# PowerBoard.net
KiCad netlist of a schematic drawn in Altium Designer
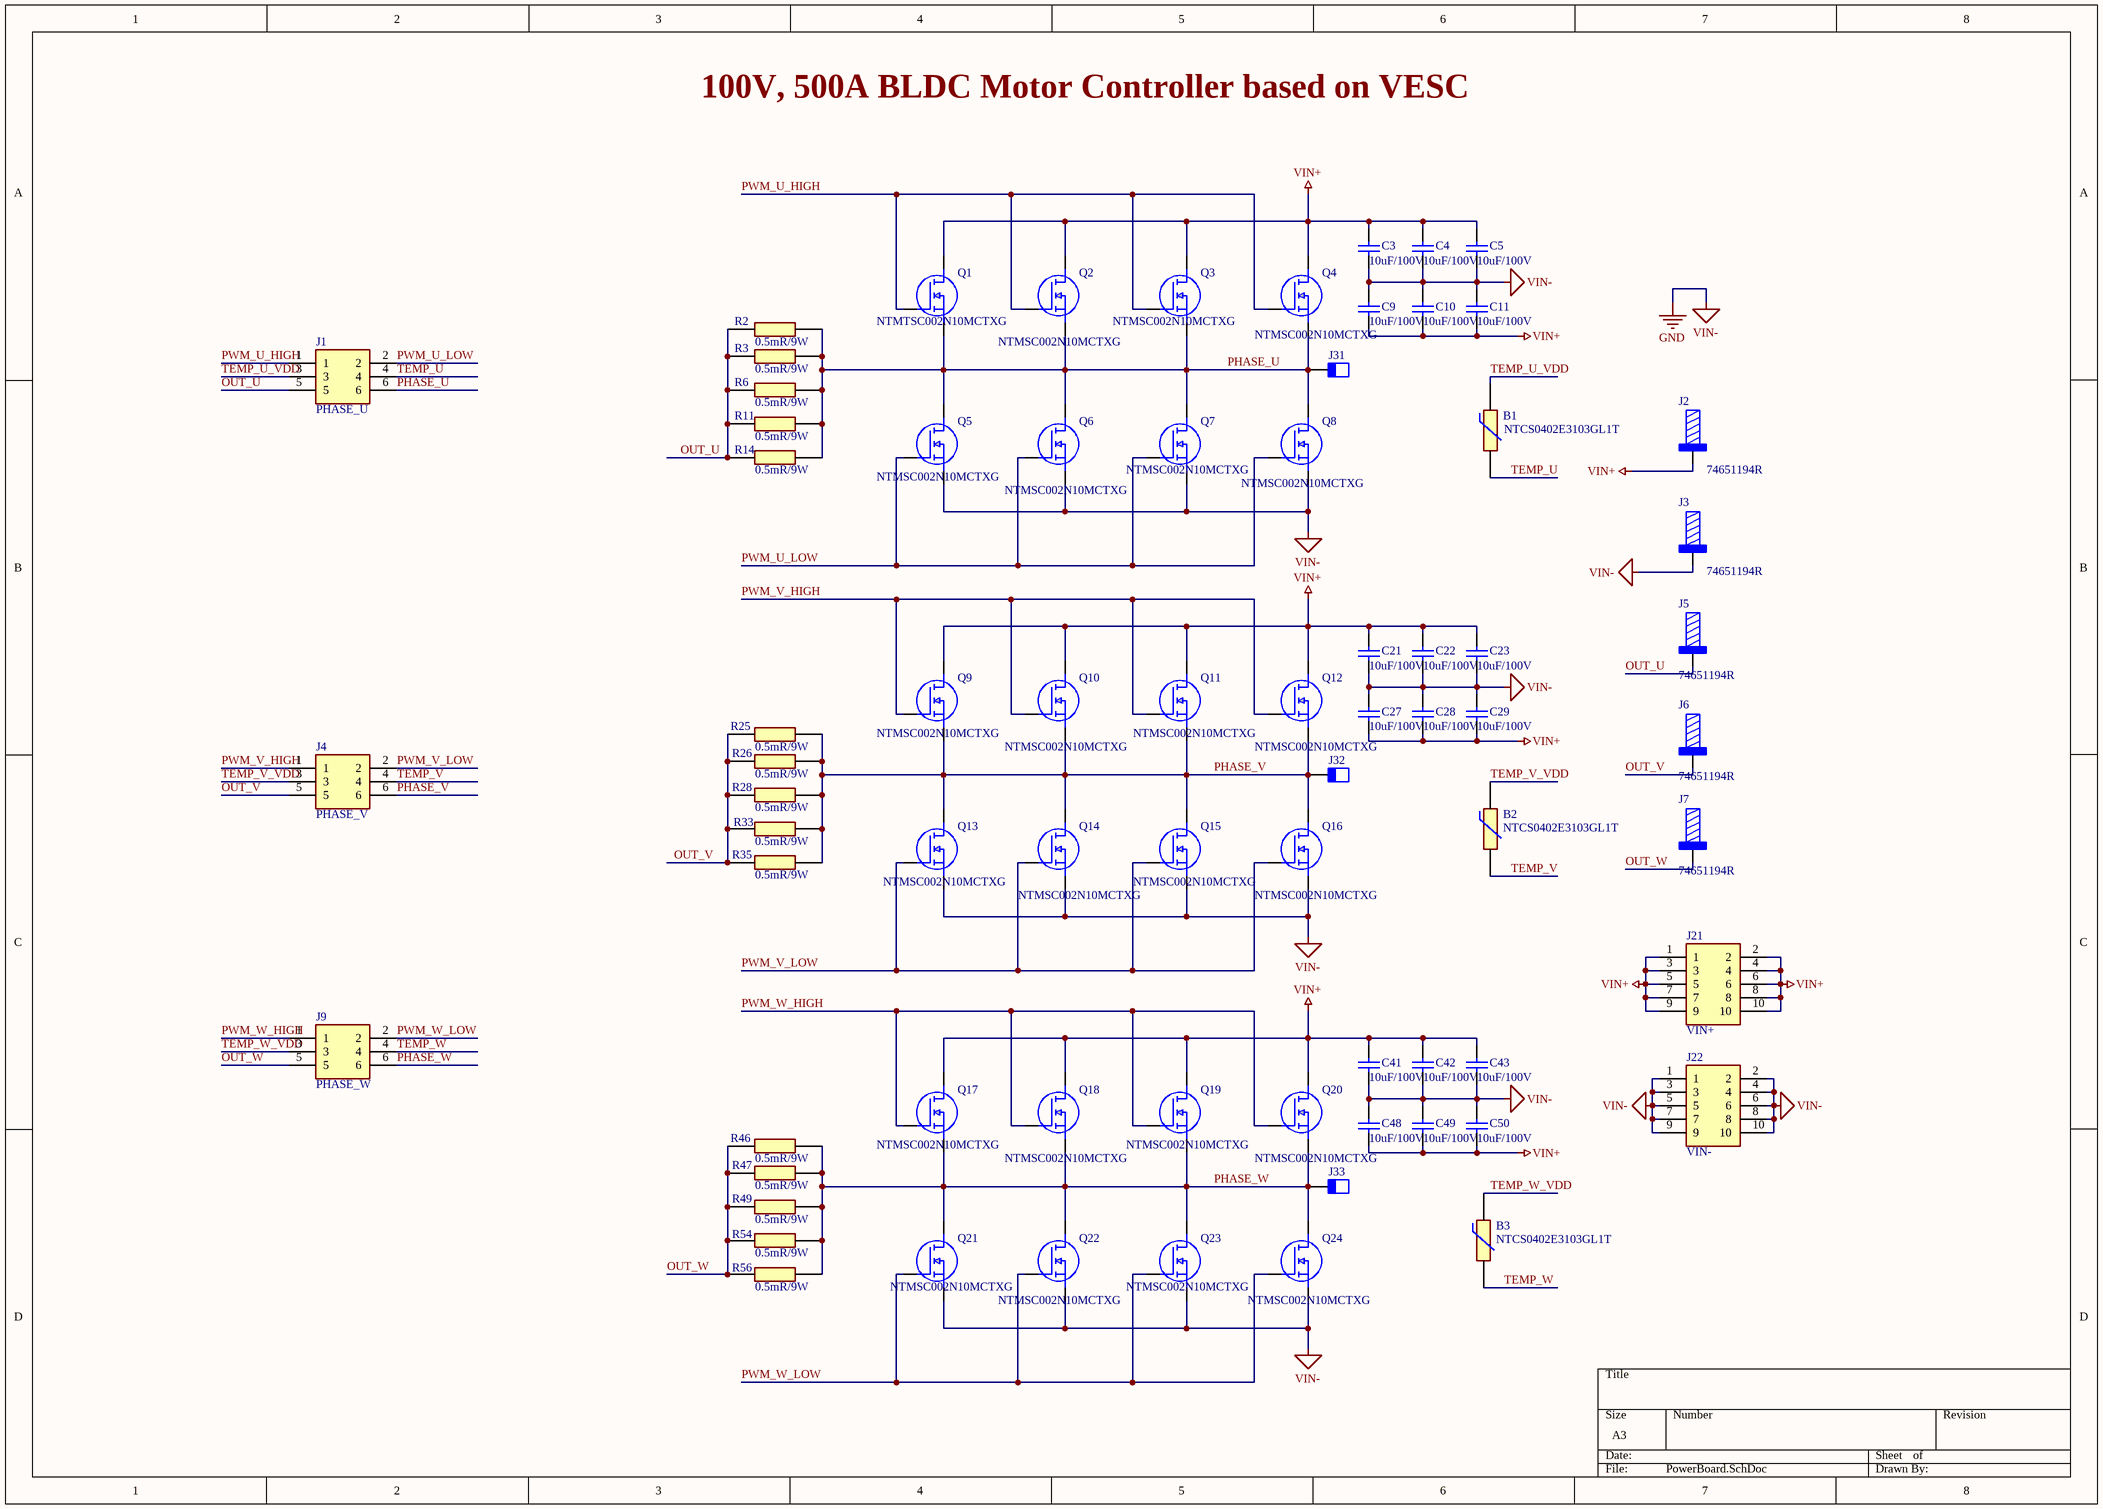
[diagram p0: PowerBoard.SchDoc]

(export (version "E")
  (design (tool "Eeschema 10.0.6"))
  (components
    (comp (ref "B1")
      (value "NTCS0402E3103GL1T")
      (footprint "THRMC1005X65N")
      (description "NTC Thermistors 10Kohms 2% AEC-Q200")
      (fields (field (name "MANUFACTURER") "Vishay"))
      (libsource (lib "VESC_MotorController") (part "NTCS0402E3103GL1T"))
    )
    (comp (ref "B2")
      (value "NTCS0402E3103GL1T")
      (footprint "THRMC1005X65N")
      (description "NTC Thermistors 10Kohms 2% AEC-Q200")
      (fields (field (name "MANUFACTURER") "Vishay"))
      (libsource (lib "VESC_MotorController") (part "NTCS0402E3103GL1T"))
    )
    (comp (ref "B3")
      (value "NTCS0402E3103GL1T")
      (footprint "THRMC1005X65N")
      (description "NTC Thermistors 10Kohms 2% AEC-Q200")
      (fields (field (name "MANUFACTURER") "Vishay"))
      (libsource (lib "VESC_MotorController") (part "NTCS0402E3103GL1T"))
    )
    (comp (ref "C3")
      (value "10uF/100V")
      (footprint "CAPC3225X230N")
      (description "Multilayer Ceramic Capacitors MLCC - SMD/SMT 1210 100VDC 10uF 10% X7R")
      (fields
        (field (name "MANUFACTURER") "TDK")
        (field (name "MANUFACTURER PART NUMBER") "C3225X7R2A106K250AC")
      )
      (libsource (lib "VESC_MotorController") (part "10uF ± 10% 100V"))
    )
    (comp (ref "C4")
      (value "10uF/100V")
      (footprint "CAPC3225X230N")
      (description "Multilayer Ceramic Capacitors MLCC - SMD/SMT 1210 100VDC 10uF 10% X7R")
      (fields
        (field (name "MANUFACTURER") "TDK")
        (field (name "MANUFACTURER PART NUMBER") "C3225X7R2A106K250AC")
      )
      (libsource (lib "VESC_MotorController") (part "10uF ± 10% 100V"))
    )
    (comp (ref "C5")
      (value "10uF/100V")
      (footprint "CAPC3225X230N")
      (description "Multilayer Ceramic Capacitors MLCC - SMD/SMT 1210 100VDC 10uF 10% X7R")
      (fields
        (field (name "MANUFACTURER") "TDK")
        (field (name "MANUFACTURER PART NUMBER") "C3225X7R2A106K250AC")
      )
      (libsource (lib "VESC_MotorController") (part "10uF ± 10% 100V"))
    )
    (comp (ref "C9")
      (value "10uF/100V")
      (footprint "CAPC3225X230N")
      (description "Multilayer Ceramic Capacitors MLCC - SMD/SMT 1210 100VDC 10uF 10% X7R")
      (fields
        (field (name "MANUFACTURER") "TDK")
        (field (name "MANUFACTURER PART NUMBER") "C3225X7R2A106K250AC")
      )
      (libsource (lib "VESC_MotorController") (part "10uF ± 10% 100V"))
    )
    (comp (ref "C10")
      (value "10uF/100V")
      (footprint "CAPC3225X230N")
      (description "Multilayer Ceramic Capacitors MLCC - SMD/SMT 1210 100VDC 10uF 10% X7R")
      (fields
        (field (name "MANUFACTURER") "TDK")
        (field (name "MANUFACTURER PART NUMBER") "C3225X7R2A106K250AC")
      )
      (libsource (lib "VESC_MotorController") (part "10uF ± 10% 100V"))
    )
    (comp (ref "C11")
      (value "10uF/100V")
      (footprint "CAPC3225X230N")
      (description "Multilayer Ceramic Capacitors MLCC - SMD/SMT 1210 100VDC 10uF 10% X7R")
      (fields
        (field (name "MANUFACTURER") "TDK")
        (field (name "MANUFACTURER PART NUMBER") "C3225X7R2A106K250AC")
      )
      (libsource (lib "VESC_MotorController") (part "10uF ± 10% 100V"))
    )
    (comp (ref "C21")
      (value "10uF/100V")
      (footprint "CAPC3225X230N")
      (description "Multilayer Ceramic Capacitors MLCC - SMD/SMT 1210 100VDC 10uF 10% X7R")
      (fields
        (field (name "MANUFACTURER") "TDK")
        (field (name "MANUFACTURER PART NUMBER") "C3225X7R2A106K250AC")
      )
      (libsource (lib "VESC_MotorController") (part "10uF ± 10% 100V"))
    )
    (comp (ref "C22")
      (value "10uF/100V")
      (footprint "CAPC3225X230N")
      (description "Multilayer Ceramic Capacitors MLCC - SMD/SMT 1210 100VDC 10uF 10% X7R")
      (fields
        (field (name "MANUFACTURER") "TDK")
        (field (name "MANUFACTURER PART NUMBER") "C3225X7R2A106K250AC")
      )
      (libsource (lib "VESC_MotorController") (part "10uF ± 10% 100V"))
    )
    (comp (ref "C23")
      (value "10uF/100V")
      (footprint "CAPC3225X230N")
      (description "Multilayer Ceramic Capacitors MLCC - SMD/SMT 1210 100VDC 10uF 10% X7R")
      (fields
        (field (name "MANUFACTURER") "TDK")
        (field (name "MANUFACTURER PART NUMBER") "C3225X7R2A106K250AC")
      )
      (libsource (lib "VESC_MotorController") (part "10uF ± 10% 100V"))
    )
    (comp (ref "C27")
      (value "10uF/100V")
      (footprint "CAPC3225X230N")
      (description "Multilayer Ceramic Capacitors MLCC - SMD/SMT 1210 100VDC 10uF 10% X7R")
      (fields
        (field (name "MANUFACTURER") "TDK")
        (field (name "MANUFACTURER PART NUMBER") "C3225X7R2A106K250AC")
      )
      (libsource (lib "VESC_MotorController") (part "10uF ± 10% 100V"))
    )
    (comp (ref "C28")
      (value "10uF/100V")
      (footprint "CAPC3225X230N")
      (description "Multilayer Ceramic Capacitors MLCC - SMD/SMT 1210 100VDC 10uF 10% X7R")
      (fields
        (field (name "MANUFACTURER") "TDK")
        (field (name "MANUFACTURER PART NUMBER") "C3225X7R2A106K250AC")
      )
      (libsource (lib "VESC_MotorController") (part "10uF ± 10% 100V"))
    )
    (comp (ref "C29")
      (value "10uF/100V")
      (footprint "CAPC3225X230N")
      (description "Multilayer Ceramic Capacitors MLCC - SMD/SMT 1210 100VDC 10uF 10% X7R")
      (fields
        (field (name "MANUFACTURER") "TDK")
        (field (name "MANUFACTURER PART NUMBER") "C3225X7R2A106K250AC")
      )
      (libsource (lib "VESC_MotorController") (part "10uF ± 10% 100V"))
    )
    (comp (ref "C41")
      (value "10uF/100V")
      (footprint "CAPC3225X230N")
      (description "Multilayer Ceramic Capacitors MLCC - SMD/SMT 1210 100VDC 10uF 10% X7R")
      (fields
        (field (name "MANUFACTURER") "TDK")
        (field (name "MANUFACTURER PART NUMBER") "C3225X7R2A106K250AC")
      )
      (libsource (lib "VESC_MotorController") (part "10uF ± 10% 100V"))
    )
    (comp (ref "C42")
      (value "10uF/100V")
      (footprint "CAPC3225X230N")
      (description "Multilayer Ceramic Capacitors MLCC - SMD/SMT 1210 100VDC 10uF 10% X7R")
      (fields
        (field (name "MANUFACTURER") "TDK")
        (field (name "MANUFACTURER PART NUMBER") "C3225X7R2A106K250AC")
      )
      (libsource (lib "VESC_MotorController") (part "10uF ± 10% 100V"))
    )
    (comp (ref "C43")
      (value "10uF/100V")
      (footprint "CAPC3225X230N")
      (description "Multilayer Ceramic Capacitors MLCC - SMD/SMT 1210 100VDC 10uF 10% X7R")
      (fields
        (field (name "MANUFACTURER") "TDK")
        (field (name "MANUFACTURER PART NUMBER") "C3225X7R2A106K250AC")
      )
      (libsource (lib "VESC_MotorController") (part "10uF ± 10% 100V"))
    )
    (comp (ref "C48")
      (value "10uF/100V")
      (footprint "CAPC3225X230N")
      (description "Multilayer Ceramic Capacitors MLCC - SMD/SMT 1210 100VDC 10uF 10% X7R")
      (fields
        (field (name "MANUFACTURER") "TDK")
        (field (name "MANUFACTURER PART NUMBER") "C3225X7R2A106K250AC")
      )
      (libsource (lib "VESC_MotorController") (part "10uF ± 10% 100V"))
    )
    (comp (ref "C49")
      (value "10uF/100V")
      (footprint "CAPC3225X230N")
      (description "Multilayer Ceramic Capacitors MLCC - SMD/SMT 1210 100VDC 10uF 10% X7R")
      (fields
        (field (name "MANUFACTURER") "TDK")
        (field (name "MANUFACTURER PART NUMBER") "C3225X7R2A106K250AC")
      )
      (libsource (lib "VESC_MotorController") (part "10uF ± 10% 100V"))
    )
    (comp (ref "C50")
      (value "10uF/100V")
      (footprint "CAPC3225X230N")
      (description "Multilayer Ceramic Capacitors MLCC - SMD/SMT 1210 100VDC 10uF 10% X7R")
      (fields
        (field (name "MANUFACTURER") "TDK")
        (field (name "MANUFACTURER PART NUMBER") "C3225X7R2A106K250AC")
      )
      (libsource (lib "VESC_MotorController") (part "10uF ± 10% 100V"))
    )
    (comp (ref "J1")
      (value "PHASE_U")
      (footprint "61030621821")
      (description "Headers & Wire Housings WERI Header 2,54 mm SMT")
      (fields
        (field (name "MANUFACTURER") "Wurth Elektronik")
        (field (name "MANUFACTURER PART NUMBER") "61030621821")
      )
      (libsource (lib "VESC_MotorController") (part "Female Header 6 Pin_1"))
    )
    (comp (ref "J2")
      (value "74651194R")
      (footprint "COPPER_CON1")
      (description "WP-THRSH REDCUBE THR with external thread, M4 x 5mm, 85A")
      (fields (field (name "MANUFACTURER") "Wurth Elektronik"))
      (libsource (lib "VESC_MotorController") (part "CopperCon1"))
    )
    (comp (ref "J3")
      (value "74651194R")
      (footprint "COPPER_CON1")
      (description "WP-THRSH REDCUBE THR with external thread, M4 x 5mm, 85A")
      (fields (field (name "MANUFACTURER") "Wurth Elektronik"))
      (libsource (lib "VESC_MotorController") (part "CopperCon1"))
    )
    (comp (ref "J4")
      (value "PHASE_V")
      (footprint "61030621821")
      (description "Headers & Wire Housings WERI Header 2,54 mm SMT")
      (fields
        (field (name "MANUFACTURER") "Wurth Elektronik")
        (field (name "MANUFACTURER PART NUMBER") "61030621821")
      )
      (libsource (lib "VESC_MotorController") (part "Female Header 6 Pin_1"))
    )
    (comp (ref "J5")
      (value "74651194R")
      (footprint "COPPER_CON3")
      (description "WP-THRSH REDCUBE THR with external thread, M4 x 5mm, 85A")
      (fields (field (name "MANUFACTURER") "Wurth Elektronik"))
      (libsource (lib "VESC_MotorController") (part "CopperCon3"))
    )
    (comp (ref "J6")
      (value "74651194R")
      (footprint "COPPER_CON3")
      (description "WP-THRSH REDCUBE THR with external thread, M4 x 5mm, 85A")
      (fields (field (name "MANUFACTURER") "Wurth Elektronik"))
      (libsource (lib "VESC_MotorController") (part "CopperCon3"))
    )
    (comp (ref "J7")
      (value "74651194R")
      (footprint "COPPER_CON3")
      (description "WP-THRSH REDCUBE THR with external thread, M4 x 5mm, 85A")
      (fields (field (name "MANUFACTURER") "Wurth Elektronik"))
      (libsource (lib "VESC_MotorController") (part "CopperCon3"))
    )
    (comp (ref "J9")
      (value "PHASE_W")
      (footprint "61030621821")
      (description "Headers & Wire Housings WERI Header 2,54 mm SMT")
      (fields
        (field (name "MANUFACTURER") "Wurth Elektronik")
        (field (name "MANUFACTURER PART NUMBER") "61030621821")
      )
      (libsource (lib "VESC_MotorController") (part "Female Header 6 Pin_1"))
    )
    (comp (ref "J21")
      (value "VIN+")
      (footprint "61031021821")
      (description "Headers & Wire Housings WR-PHD 250VAC 3A Gry 2Row 10Pos Strgt")
      (fields
        (field (name "MANUFACTURER") "Wurth Elektronik")
        (field (name "MANUFACTURER PART NUMBER") "61031021821")
      )
      (libsource (lib "VESC_MotorController") (part "Female Header 10 Pin_1"))
    )
    (comp (ref "J22")
      (value "VIN-")
      (footprint "61031021821")
      (description "Headers & Wire Housings WR-PHD 250VAC 3A Gry 2Row 10Pos Strgt")
      (fields
        (field (name "MANUFACTURER") "Wurth Elektronik")
        (field (name "MANUFACTURER PART NUMBER") "61031021821")
      )
      (libsource (lib "VESC_MotorController") (part "Female Header 10 Pin_1"))
    )
    (comp (ref "J31")
      (value "~")
      (footprint "COPPER_BUS")
      (description "WP-THRSH REDCUBE THR with external thread, M4 x 5mm, 85A")
      (fields
        (field (name "MANUFACTURER PART NUMBER") "74651194R")
        (field (name "MANUFACTURER") "Wurth Elektronik")
      )
      (libsource (lib "VESC_MotorController") (part "CopperBus"))
    )
    (comp (ref "J32")
      (value "~")
      (footprint "COPPER_BUS")
      (description "WP-THRSH REDCUBE THR with external thread, M4 x 5mm, 85A")
      (fields
        (field (name "MANUFACTURER PART NUMBER") "74651194R")
        (field (name "MANUFACTURER") "Wurth Elektronik")
      )
      (libsource (lib "VESC_MotorController") (part "CopperBus"))
    )
    (comp (ref "J33")
      (value "~")
      (footprint "COPPER_BUS")
      (description "WP-THRSH REDCUBE THR with external thread, M4 x 5mm, 85A")
      (fields
        (field (name "MANUFACTURER PART NUMBER") "74651194R")
        (field (name "MANUFACTURER") "Wurth Elektronik")
      )
      (libsource (lib "VESC_MotorController") (part "CopperBus"))
    )
    (comp (ref "Q1")
      (value "NTMTSC002N10MCTXG")
      (footprint "NTMSC002N10MCTXG")
      (description "MOSFET Single N-Channel Power MOSFET 100V, 236A, 2.0mohm")
      (fields (field (name "MANUFACTURER") "Onsemi"))
      (libsource (lib "VESC_MotorController") (part "NTMSC002N10MCTXG"))
    )
    (comp (ref "Q2")
      (value "NTMSC002N10MCTXG")
      (footprint "NTMSC002N10MCTXG")
      (description "MOSFET Single N-Channel Power MOSFET 100V, 236A, 2.0mohm")
      (fields
        (field (name "MANUFACTURER") "Onsemi")
        (field (name "MANUFACTURER PART NUMBER") "NTMTSC002N10MCTXG")
      )
      (libsource (lib "VESC_MotorController") (part "NTMSC002N10MCTXG"))
    )
    (comp (ref "Q3")
      (value "NTMSC002N10MCTXG")
      (footprint "NTMSC002N10MCTXG")
      (description "MOSFET Single N-Channel Power MOSFET 100V, 236A, 2.0mohm")
      (fields
        (field (name "MANUFACTURER") "Onsemi")
        (field (name "MANUFACTURER PART NUMBER") "NTMTSC002N10MCTXG")
      )
      (libsource (lib "VESC_MotorController") (part "NTMSC002N10MCTXG"))
    )
    (comp (ref "Q4")
      (value "NTMSC002N10MCTXG")
      (footprint "NTMSC002N10MCTXG")
      (description "MOSFET Single N-Channel Power MOSFET 100V, 236A, 2.0mohm")
      (fields
        (field (name "MANUFACTURER") "Onsemi")
        (field (name "MANUFACTURER PART NUMBER") "NTMTSC002N10MCTXG")
      )
      (libsource (lib "VESC_MotorController") (part "NTMSC002N10MCTXG"))
    )
    (comp (ref "Q5")
      (value "NTMSC002N10MCTXG")
      (footprint "NTMSC002N10MCTXG")
      (description "MOSFET Single N-Channel Power MOSFET 100V, 236A, 2.0mohm")
      (fields
        (field (name "MANUFACTURER") "Onsemi")
        (field (name "MANUFACTURER PART NUMBER") "NTMTSC002N10MCTXG")
      )
      (libsource (lib "VESC_MotorController") (part "NTMSC002N10MCTXG"))
    )
    (comp (ref "Q6")
      (value "NTMSC002N10MCTXG")
      (footprint "NTMSC002N10MCTXG")
      (description "MOSFET Single N-Channel Power MOSFET 100V, 236A, 2.0mohm")
      (fields
        (field (name "MANUFACTURER") "Onsemi")
        (field (name "MANUFACTURER PART NUMBER") "NTMTSC002N10MCTXG")
      )
      (libsource (lib "VESC_MotorController") (part "NTMSC002N10MCTXG"))
    )
    (comp (ref "Q7")
      (value "NTMSC002N10MCTXG")
      (footprint "NTMSC002N10MCTXG")
      (description "MOSFET Single N-Channel Power MOSFET 100V, 236A, 2.0mohm")
      (fields
        (field (name "MANUFACTURER") "Onsemi")
        (field (name "MANUFACTURER PART NUMBER") "NTMTSC002N10MCTXG")
      )
      (libsource (lib "VESC_MotorController") (part "NTMSC002N10MCTXG"))
    )
    (comp (ref "Q8")
      (value "NTMSC002N10MCTXG")
      (footprint "NTMSC002N10MCTXG")
      (description "MOSFET Single N-Channel Power MOSFET 100V, 236A, 2.0mohm")
      (fields
        (field (name "MANUFACTURER") "Onsemi")
        (field (name "MANUFACTURER PART NUMBER") "NTMTSC002N10MCTXG")
      )
      (libsource (lib "VESC_MotorController") (part "NTMSC002N10MCTXG"))
    )
    (comp (ref "Q9")
      (value "NTMSC002N10MCTXG")
      (footprint "NTMSC002N10MCTXG")
      (description "MOSFET Single N-Channel Power MOSFET 100V, 236A, 2.0mohm")
      (fields
        (field (name "MANUFACTURER") "Onsemi")
        (field (name "MANUFACTURER PART NUMBER") "NTMTSC002N10MCTXG")
      )
      (libsource (lib "VESC_MotorController") (part "NTMSC002N10MCTXG"))
    )
    (comp (ref "Q10")
      (value "NTMSC002N10MCTXG")
      (footprint "NTMSC002N10MCTXG")
      (description "MOSFET Single N-Channel Power MOSFET 100V, 236A, 2.0mohm")
      (fields
        (field (name "MANUFACTURER") "Onsemi")
        (field (name "MANUFACTURER PART NUMBER") "NTMTSC002N10MCTXG")
      )
      (libsource (lib "VESC_MotorController") (part "NTMSC002N10MCTXG"))
    )
    (comp (ref "Q11")
      (value "NTMSC002N10MCTXG")
      (footprint "NTMSC002N10MCTXG")
      (description "MOSFET Single N-Channel Power MOSFET 100V, 236A, 2.0mohm")
      (fields
        (field (name "MANUFACTURER") "Onsemi")
        (field (name "MANUFACTURER PART NUMBER") "NTMTSC002N10MCTXG")
      )
      (libsource (lib "VESC_MotorController") (part "NTMSC002N10MCTXG"))
    )
    (comp (ref "Q12")
      (value "NTMSC002N10MCTXG")
      (footprint "NTMSC002N10MCTXG")
      (description "MOSFET Single N-Channel Power MOSFET 100V, 236A, 2.0mohm")
      (fields
        (field (name "MANUFACTURER") "Onsemi")
        (field (name "MANUFACTURER PART NUMBER") "NTMTSC002N10MCTXG")
      )
      (libsource (lib "VESC_MotorController") (part "NTMSC002N10MCTXG"))
    )
    (comp (ref "Q13")
      (value "NTMSC002N10MCTXG")
      (footprint "NTMSC002N10MCTXG")
      (description "MOSFET Single N-Channel Power MOSFET 100V, 236A, 2.0mohm")
      (fields
        (field (name "MANUFACTURER") "Onsemi")
        (field (name "MANUFACTURER PART NUMBER") "NTMTSC002N10MCTXG")
      )
      (libsource (lib "VESC_MotorController") (part "NTMSC002N10MCTXG"))
    )
    (comp (ref "Q14")
      (value "NTMSC002N10MCTXG")
      (footprint "NTMSC002N10MCTXG")
      (description "MOSFET Single N-Channel Power MOSFET 100V, 236A, 2.0mohm")
      (fields
        (field (name "MANUFACTURER") "Onsemi")
        (field (name "MANUFACTURER PART NUMBER") "NTMTSC002N10MCTXG")
      )
      (libsource (lib "VESC_MotorController") (part "NTMSC002N10MCTXG"))
    )
    (comp (ref "Q15")
      (value "NTMSC002N10MCTXG")
      (footprint "NTMSC002N10MCTXG")
      (description "MOSFET Single N-Channel Power MOSFET 100V, 236A, 2.0mohm")
      (fields
        (field (name "MANUFACTURER") "Onsemi")
        (field (name "MANUFACTURER PART NUMBER") "NTMTSC002N10MCTXG")
      )
      (libsource (lib "VESC_MotorController") (part "NTMSC002N10MCTXG"))
    )
    (comp (ref "Q16")
      (value "NTMSC002N10MCTXG")
      (footprint "NTMSC002N10MCTXG")
      (description "MOSFET Single N-Channel Power MOSFET 100V, 236A, 2.0mohm")
      (fields
        (field (name "MANUFACTURER") "Onsemi")
        (field (name "MANUFACTURER PART NUMBER") "NTMTSC002N10MCTXG")
      )
      (libsource (lib "VESC_MotorController") (part "NTMSC002N10MCTXG"))
    )
    (comp (ref "Q17")
      (value "NTMSC002N10MCTXG")
      (footprint "NTMSC002N10MCTXG")
      (description "MOSFET Single N-Channel Power MOSFET 100V, 236A, 2.0mohm")
      (fields
        (field (name "MANUFACTURER") "Onsemi")
        (field (name "MANUFACTURER PART NUMBER") "NTMTSC002N10MCTXG")
      )
      (libsource (lib "VESC_MotorController") (part "NTMSC002N10MCTXG"))
    )
    (comp (ref "Q18")
      (value "NTMSC002N10MCTXG")
      (footprint "NTMSC002N10MCTXG")
      (description "MOSFET Single N-Channel Power MOSFET 100V, 236A, 2.0mohm")
      (fields
        (field (name "MANUFACTURER") "Onsemi")
        (field (name "MANUFACTURER PART NUMBER") "NTMTSC002N10MCTXG")
      )
      (libsource (lib "VESC_MotorController") (part "NTMSC002N10MCTXG"))
    )
    (comp (ref "Q19")
      (value "NTMSC002N10MCTXG")
      (footprint "NTMSC002N10MCTXG")
      (description "MOSFET Single N-Channel Power MOSFET 100V, 236A, 2.0mohm")
      (fields
        (field (name "MANUFACTURER") "Onsemi")
        (field (name "MANUFACTURER PART NUMBER") "NTMTSC002N10MCTXG")
      )
      (libsource (lib "VESC_MotorController") (part "NTMSC002N10MCTXG"))
    )
    (comp (ref "Q20")
      (value "NTMSC002N10MCTXG")
      (footprint "NTMSC002N10MCTXG")
      (description "MOSFET Single N-Channel Power MOSFET 100V, 236A, 2.0mohm")
      (fields
        (field (name "MANUFACTURER") "Onsemi")
        (field (name "MANUFACTURER PART NUMBER") "NTMTSC002N10MCTXG")
      )
      (libsource (lib "VESC_MotorController") (part "NTMSC002N10MCTXG"))
    )
    (comp (ref "Q21")
      (value "NTMSC002N10MCTXG")
      (footprint "NTMSC002N10MCTXG")
      (description "MOSFET Single N-Channel Power MOSFET 100V, 236A, 2.0mohm")
      (fields
        (field (name "MANUFACTURER") "Onsemi")
        (field (name "MANUFACTURER PART NUMBER") "NTMTSC002N10MCTXG")
      )
      (libsource (lib "VESC_MotorController") (part "NTMSC002N10MCTXG"))
    )
    (comp (ref "Q22")
      (value "NTMSC002N10MCTXG")
      (footprint "NTMSC002N10MCTXG")
      (description "MOSFET Single N-Channel Power MOSFET 100V, 236A, 2.0mohm")
      (fields
        (field (name "MANUFACTURER") "Onsemi")
        (field (name "MANUFACTURER PART NUMBER") "NTMTSC002N10MCTXG")
      )
      (libsource (lib "VESC_MotorController") (part "NTMSC002N10MCTXG"))
    )
    (comp (ref "Q23")
      (value "NTMSC002N10MCTXG")
      (footprint "NTMSC002N10MCTXG")
      (description "MOSFET Single N-Channel Power MOSFET 100V, 236A, 2.0mohm")
      (fields
        (field (name "MANUFACTURER") "Onsemi")
        (field (name "MANUFACTURER PART NUMBER") "NTMTSC002N10MCTXG")
      )
      (libsource (lib "VESC_MotorController") (part "NTMSC002N10MCTXG"))
    )
    (comp (ref "Q24")
      (value "NTMSC002N10MCTXG")
      (footprint "NTMSC002N10MCTXG")
      (description "MOSFET Single N-Channel Power MOSFET 100V, 236A, 2.0mohm")
      (fields
        (field (name "MANUFACTURER") "Onsemi")
        (field (name "MANUFACTURER PART NUMBER") "NTMTSC002N10MCTXG")
      )
      (libsource (lib "VESC_MotorController") (part "NTMSC002N10MCTXG"))
    )
    (comp (ref "R2")
      (value "0.5mR/9W")
      (footprint "RESC10052X137N")
      (description "Current Sense Resistors - SMD 0.5mOHMS 9W 1% AEC-Q200")
      (fields
        (field (name "MANUFACTURER") "Bourns")
        (field (name "MANUFACTURER PART NUMBER") "CSS2H-3920R-L500FE")
      )
      (libsource (lib "VESC_MotorController") (part "CSS2H-3920R-L500FE"))
    )
    (comp (ref "R3")
      (value "0.5mR/9W")
      (footprint "RESC10052X137N")
      (description "Current Sense Resistors - SMD 0.5mOHMS 9W 1% AEC-Q200")
      (fields
        (field (name "MANUFACTURER") "Bourns")
        (field (name "MANUFACTURER PART NUMBER") "CSS2H-3920R-L500FE")
      )
      (libsource (lib "VESC_MotorController") (part "CSS2H-3920R-L500FE"))
    )
    (comp (ref "R6")
      (value "0.5mR/9W")
      (footprint "RESC10052X137N")
      (description "Current Sense Resistors - SMD 0.5mOHMS 9W 1% AEC-Q200")
      (fields
        (field (name "MANUFACTURER") "Bourns")
        (field (name "MANUFACTURER PART NUMBER") "CSS2H-3920R-L500FE")
      )
      (libsource (lib "VESC_MotorController") (part "CSS2H-3920R-L500FE"))
    )
    (comp (ref "R11")
      (value "0.5mR/9W")
      (footprint "RESC10052X137N")
      (description "Current Sense Resistors - SMD 0.5mOHMS 9W 1% AEC-Q200")
      (fields
        (field (name "MANUFACTURER") "Bourns")
        (field (name "MANUFACTURER PART NUMBER") "CSS2H-3920R-L500FE")
      )
      (libsource (lib "VESC_MotorController") (part "CSS2H-3920R-L500FE"))
    )
    (comp (ref "R14")
      (value "0.5mR/9W")
      (footprint "RESC10052X137N")
      (description "Current Sense Resistors - SMD 0.5mOHMS 9W 1% AEC-Q200")
      (fields
        (field (name "MANUFACTURER") "Bourns")
        (field (name "MANUFACTURER PART NUMBER") "CSS2H-3920R-L500FE")
      )
      (libsource (lib "VESC_MotorController") (part "CSS2H-3920R-L500FE"))
    )
    (comp (ref "R25")
      (value "0.5mR/9W")
      (footprint "RESC10052X137N")
      (description "Current Sense Resistors - SMD 0.5mOHMS 9W 1% AEC-Q200")
      (fields
        (field (name "MANUFACTURER") "Bourns")
        (field (name "MANUFACTURER PART NUMBER") "CSS2H-3920R-L500FE")
      )
      (libsource (lib "VESC_MotorController") (part "CSS2H-3920R-L500FE"))
    )
    (comp (ref "R26")
      (value "0.5mR/9W")
      (footprint "RESC10052X137N")
      (description "Current Sense Resistors - SMD 0.5mOHMS 9W 1% AEC-Q200")
      (fields
        (field (name "MANUFACTURER") "Bourns")
        (field (name "MANUFACTURER PART NUMBER") "CSS2H-3920R-L500FE")
      )
      (libsource (lib "VESC_MotorController") (part "CSS2H-3920R-L500FE"))
    )
    (comp (ref "R28")
      (value "0.5mR/9W")
      (footprint "RESC10052X137N")
      (description "Current Sense Resistors - SMD 0.5mOHMS 9W 1% AEC-Q200")
      (fields
        (field (name "MANUFACTURER") "Bourns")
        (field (name "MANUFACTURER PART NUMBER") "CSS2H-3920R-L500FE")
      )
      (libsource (lib "VESC_MotorController") (part "CSS2H-3920R-L500FE"))
    )
    (comp (ref "R33")
      (value "0.5mR/9W")
      (footprint "RESC10052X137N")
      (description "Current Sense Resistors - SMD 0.5mOHMS 9W 1% AEC-Q200")
      (fields
        (field (name "MANUFACTURER") "Bourns")
        (field (name "MANUFACTURER PART NUMBER") "CSS2H-3920R-L500FE")
      )
      (libsource (lib "VESC_MotorController") (part "CSS2H-3920R-L500FE"))
    )
    (comp (ref "R35")
      (value "0.5mR/9W")
      (footprint "RESC10052X137N")
      (description "Current Sense Resistors - SMD 0.5mOHMS 9W 1% AEC-Q200")
      (fields
        (field (name "MANUFACTURER") "Bourns")
        (field (name "MANUFACTURER PART NUMBER") "CSS2H-3920R-L500FE")
      )
      (libsource (lib "VESC_MotorController") (part "CSS2H-3920R-L500FE"))
    )
    (comp (ref "R46")
      (value "0.5mR/9W")
      (footprint "RESC10052X137N")
      (description "Current Sense Resistors - SMD 0.5mOHMS 9W 1% AEC-Q200")
      (fields
        (field (name "MANUFACTURER") "Bourns")
        (field (name "MANUFACTURER PART NUMBER") "CSS2H-3920R-L500FE")
      )
      (libsource (lib "VESC_MotorController") (part "CSS2H-3920R-L500FE"))
    )
    (comp (ref "R47")
      (value "0.5mR/9W")
      (footprint "RESC10052X137N")
      (description "Current Sense Resistors - SMD 0.5mOHMS 9W 1% AEC-Q200")
      (fields
        (field (name "MANUFACTURER") "Bourns")
        (field (name "MANUFACTURER PART NUMBER") "CSS2H-3920R-L500FE")
      )
      (libsource (lib "VESC_MotorController") (part "CSS2H-3920R-L500FE"))
    )
    (comp (ref "R49")
      (value "0.5mR/9W")
      (footprint "RESC10052X137N")
      (description "Current Sense Resistors - SMD 0.5mOHMS 9W 1% AEC-Q200")
      (fields
        (field (name "MANUFACTURER") "Bourns")
        (field (name "MANUFACTURER PART NUMBER") "CSS2H-3920R-L500FE")
      )
      (libsource (lib "VESC_MotorController") (part "CSS2H-3920R-L500FE"))
    )
    (comp (ref "R54")
      (value "0.5mR/9W")
      (footprint "RESC10052X137N")
      (description "Current Sense Resistors - SMD 0.5mOHMS 9W 1% AEC-Q200")
      (fields
        (field (name "MANUFACTURER") "Bourns")
        (field (name "MANUFACTURER PART NUMBER") "CSS2H-3920R-L500FE")
      )
      (libsource (lib "VESC_MotorController") (part "CSS2H-3920R-L500FE"))
    )
    (comp (ref "R56")
      (value "0.5mR/9W")
      (footprint "RESC10052X137N")
      (description "Current Sense Resistors - SMD 0.5mOHMS 9W 1% AEC-Q200")
      (fields
        (field (name "MANUFACTURER") "Bourns")
        (field (name "MANUFACTURER PART NUMBER") "CSS2H-3920R-L500FE")
      )
      (libsource (lib "VESC_MotorController") (part "CSS2H-3920R-L500FE"))
    )
  )
  (nets
    (net (code "1") (name "/OUT_U") (class "Default")
      (node (ref "J1") (pin "5") (pinfunction "5_5") (pintype "passive"))
      (node (ref "J5") (pin "1") (pinfunction "1_1") (pintype "passive"))
      (node (ref "R11") (pin "1") (pinfunction "1_1") (pintype "passive"))
      (node (ref "R14") (pin "1") (pinfunction "1_1") (pintype "passive"))
      (node (ref "R2") (pin "1") (pinfunction "1_1") (pintype "passive"))
      (node (ref "R3") (pin "1") (pinfunction "1_1") (pintype "passive"))
      (node (ref "R6") (pin "1") (pinfunction "1_1") (pintype "passive"))
    )
    (net (code "2") (name "/OUT_V") (class "Default")
      (node (ref "J4") (pin "5") (pinfunction "5_5") (pintype "passive"))
      (node (ref "J6") (pin "1") (pinfunction "1_1") (pintype "passive"))
      (node (ref "R25") (pin "1") (pinfunction "1_1") (pintype "passive"))
      (node (ref "R26") (pin "1") (pinfunction "1_1") (pintype "passive"))
      (node (ref "R28") (pin "1") (pinfunction "1_1") (pintype "passive"))
      (node (ref "R33") (pin "1") (pinfunction "1_1") (pintype "passive"))
      (node (ref "R35") (pin "1") (pinfunction "1_1") (pintype "passive"))
    )
    (net (code "3") (name "/OUT_W") (class "Default")
      (node (ref "J7") (pin "1") (pinfunction "1_1") (pintype "passive"))
      (node (ref "J9") (pin "5") (pinfunction "5_5") (pintype "passive"))
      (node (ref "R46") (pin "1") (pinfunction "1_1") (pintype "passive"))
      (node (ref "R47") (pin "1") (pinfunction "1_1") (pintype "passive"))
      (node (ref "R49") (pin "1") (pinfunction "1_1") (pintype "passive"))
      (node (ref "R54") (pin "1") (pinfunction "1_1") (pintype "passive"))
      (node (ref "R56") (pin "1") (pinfunction "1_1") (pintype "passive"))
    )
    (net (code "4") (name "/PHASE_U") (class "Default")
      (node (ref "J1") (pin "6") (pinfunction "6_6") (pintype "passive"))
      (node (ref "J31") (pin "1") (pinfunction "1_1") (pintype "passive"))
      (node (ref "Q1") (pin "SOURCE") (pinfunction "SOURCE_SOURCE") (pintype "passive"))
      (node (ref "Q2") (pin "SOURCE") (pinfunction "SOURCE_SOURCE") (pintype "passive"))
      (node (ref "Q3") (pin "SOURCE") (pinfunction "SOURCE_SOURCE") (pintype "passive"))
      (node (ref "Q4") (pin "SOURCE") (pinfunction "SOURCE_SOURCE") (pintype "passive"))
      (node (ref "Q5") (pin "DRAIN") (pinfunction "DRAIN_DRAIN") (pintype "passive"))
      (node (ref "Q6") (pin "DRAIN") (pinfunction "DRAIN_DRAIN") (pintype "passive"))
      (node (ref "Q7") (pin "DRAIN") (pinfunction "DRAIN_DRAIN") (pintype "passive"))
      (node (ref "Q8") (pin "DRAIN") (pinfunction "DRAIN_DRAIN") (pintype "passive"))
      (node (ref "R11") (pin "2") (pinfunction "2_2") (pintype "passive"))
      (node (ref "R14") (pin "2") (pinfunction "2_2") (pintype "passive"))
      (node (ref "R2") (pin "2") (pinfunction "2_2") (pintype "passive"))
      (node (ref "R3") (pin "2") (pinfunction "2_2") (pintype "passive"))
      (node (ref "R6") (pin "2") (pinfunction "2_2") (pintype "passive"))
    )
    (net (code "5") (name "/PHASE_V") (class "Default")
      (node (ref "J32") (pin "1") (pinfunction "1_1") (pintype "passive"))
      (node (ref "J4") (pin "6") (pinfunction "6_6") (pintype "passive"))
      (node (ref "Q10") (pin "SOURCE") (pinfunction "SOURCE_SOURCE") (pintype "passive"))
      (node (ref "Q11") (pin "SOURCE") (pinfunction "SOURCE_SOURCE") (pintype "passive"))
      (node (ref "Q12") (pin "SOURCE") (pinfunction "SOURCE_SOURCE") (pintype "passive"))
      (node (ref "Q13") (pin "DRAIN") (pinfunction "DRAIN_DRAIN") (pintype "passive"))
      (node (ref "Q14") (pin "DRAIN") (pinfunction "DRAIN_DRAIN") (pintype "passive"))
      (node (ref "Q15") (pin "DRAIN") (pinfunction "DRAIN_DRAIN") (pintype "passive"))
      (node (ref "Q16") (pin "DRAIN") (pinfunction "DRAIN_DRAIN") (pintype "passive"))
      (node (ref "Q9") (pin "SOURCE") (pinfunction "SOURCE_SOURCE") (pintype "passive"))
      (node (ref "R25") (pin "2") (pinfunction "2_2") (pintype "passive"))
      (node (ref "R26") (pin "2") (pinfunction "2_2") (pintype "passive"))
      (node (ref "R28") (pin "2") (pinfunction "2_2") (pintype "passive"))
      (node (ref "R33") (pin "2") (pinfunction "2_2") (pintype "passive"))
      (node (ref "R35") (pin "2") (pinfunction "2_2") (pintype "passive"))
    )
    (net (code "6") (name "/PHASE_W") (class "Default")
      (node (ref "J33") (pin "1") (pinfunction "1_1") (pintype "passive"))
      (node (ref "J9") (pin "6") (pinfunction "6_6") (pintype "passive"))
      (node (ref "Q17") (pin "SOURCE") (pinfunction "SOURCE_SOURCE") (pintype "passive"))
      (node (ref "Q18") (pin "SOURCE") (pinfunction "SOURCE_SOURCE") (pintype "passive"))
      (node (ref "Q19") (pin "SOURCE") (pinfunction "SOURCE_SOURCE") (pintype "passive"))
      (node (ref "Q20") (pin "SOURCE") (pinfunction "SOURCE_SOURCE") (pintype "passive"))
      (node (ref "Q21") (pin "DRAIN") (pinfunction "DRAIN_DRAIN") (pintype "passive"))
      (node (ref "Q22") (pin "DRAIN") (pinfunction "DRAIN_DRAIN") (pintype "passive"))
      (node (ref "Q23") (pin "DRAIN") (pinfunction "DRAIN_DRAIN") (pintype "passive"))
      (node (ref "Q24") (pin "DRAIN") (pinfunction "DRAIN_DRAIN") (pintype "passive"))
      (node (ref "R46") (pin "2") (pinfunction "2_2") (pintype "passive"))
      (node (ref "R47") (pin "2") (pinfunction "2_2") (pintype "passive"))
      (node (ref "R49") (pin "2") (pinfunction "2_2") (pintype "passive"))
      (node (ref "R54") (pin "2") (pinfunction "2_2") (pintype "passive"))
      (node (ref "R56") (pin "2") (pinfunction "2_2") (pintype "passive"))
    )
    (net (code "7") (name "/PWM_U_HIGH") (class "Default")
      (node (ref "J1") (pin "1") (pinfunction "1_1") (pintype "passive"))
      (node (ref "Q1") (pin "GATE") (pinfunction "GATE_GATE") (pintype "passive"))
      (node (ref "Q2") (pin "GATE") (pinfunction "GATE_GATE") (pintype "passive"))
      (node (ref "Q3") (pin "GATE") (pinfunction "GATE_GATE") (pintype "passive"))
      (node (ref "Q4") (pin "GATE") (pinfunction "GATE_GATE") (pintype "passive"))
    )
    (net (code "8") (name "/PWM_U_LOW") (class "Default")
      (node (ref "J1") (pin "2") (pinfunction "2_2") (pintype "passive"))
      (node (ref "Q5") (pin "GATE") (pinfunction "GATE_GATE") (pintype "passive"))
      (node (ref "Q6") (pin "GATE") (pinfunction "GATE_GATE") (pintype "passive"))
      (node (ref "Q7") (pin "GATE") (pinfunction "GATE_GATE") (pintype "passive"))
      (node (ref "Q8") (pin "GATE") (pinfunction "GATE_GATE") (pintype "passive"))
    )
    (net (code "9") (name "/PWM_V_HIGH") (class "Default")
      (node (ref "J4") (pin "1") (pinfunction "1_1") (pintype "passive"))
      (node (ref "Q10") (pin "GATE") (pinfunction "GATE_GATE") (pintype "passive"))
      (node (ref "Q11") (pin "GATE") (pinfunction "GATE_GATE") (pintype "passive"))
      (node (ref "Q12") (pin "GATE") (pinfunction "GATE_GATE") (pintype "passive"))
      (node (ref "Q9") (pin "GATE") (pinfunction "GATE_GATE") (pintype "passive"))
    )
    (net (code "10") (name "/PWM_V_LOW") (class "Default")
      (node (ref "J4") (pin "2") (pinfunction "2_2") (pintype "passive"))
      (node (ref "Q13") (pin "GATE") (pinfunction "GATE_GATE") (pintype "passive"))
      (node (ref "Q14") (pin "GATE") (pinfunction "GATE_GATE") (pintype "passive"))
      (node (ref "Q15") (pin "GATE") (pinfunction "GATE_GATE") (pintype "passive"))
      (node (ref "Q16") (pin "GATE") (pinfunction "GATE_GATE") (pintype "passive"))
    )
    (net (code "11") (name "/PWM_W_HIGH") (class "Default")
      (node (ref "J9") (pin "1") (pinfunction "1_1") (pintype "passive"))
      (node (ref "Q17") (pin "GATE") (pinfunction "GATE_GATE") (pintype "passive"))
      (node (ref "Q18") (pin "GATE") (pinfunction "GATE_GATE") (pintype "passive"))
      (node (ref "Q19") (pin "GATE") (pinfunction "GATE_GATE") (pintype "passive"))
      (node (ref "Q20") (pin "GATE") (pinfunction "GATE_GATE") (pintype "passive"))
    )
    (net (code "12") (name "/PWM_W_LOW") (class "Default")
      (node (ref "J9") (pin "2") (pinfunction "2_2") (pintype "passive"))
      (node (ref "Q21") (pin "GATE") (pinfunction "GATE_GATE") (pintype "passive"))
      (node (ref "Q22") (pin "GATE") (pinfunction "GATE_GATE") (pintype "passive"))
      (node (ref "Q23") (pin "GATE") (pinfunction "GATE_GATE") (pintype "passive"))
      (node (ref "Q24") (pin "GATE") (pinfunction "GATE_GATE") (pintype "passive"))
    )
    (net (code "13") (name "/TEMP_U") (class "Default")
      (node (ref "B1") (pin "2") (pinfunction "2_2") (pintype "passive"))
      (node (ref "J1") (pin "4") (pinfunction "4_4") (pintype "passive"))
    )
    (net (code "14") (name "/TEMP_U_VDD") (class "Default")
      (node (ref "B1") (pin "1") (pinfunction "1_1") (pintype "passive"))
      (node (ref "J1") (pin "3") (pinfunction "3_3") (pintype "passive"))
    )
    (net (code "15") (name "/TEMP_V") (class "Default")
      (node (ref "B2") (pin "2") (pinfunction "2_2") (pintype "passive"))
      (node (ref "J4") (pin "4") (pinfunction "4_4") (pintype "passive"))
    )
    (net (code "16") (name "/TEMP_V_VDD") (class "Default")
      (node (ref "B2") (pin "1") (pinfunction "1_1") (pintype "passive"))
      (node (ref "J4") (pin "3") (pinfunction "3_3") (pintype "passive"))
    )
    (net (code "17") (name "/TEMP_W") (class "Default")
      (node (ref "B3") (pin "2") (pinfunction "2_2") (pintype "passive"))
      (node (ref "J9") (pin "4") (pinfunction "4_4") (pintype "passive"))
    )
    (net (code "18") (name "/TEMP_W_VDD") (class "Default")
      (node (ref "B3") (pin "1") (pinfunction "1_1") (pintype "passive"))
      (node (ref "J9") (pin "3") (pinfunction "3_3") (pintype "passive"))
    )
    (net (code "19") (name "GND") (class "Default")
      (node (ref "C10") (pin "2") (pinfunction "2_2") (pintype "passive"))
      (node (ref "C11") (pin "2") (pinfunction "2_2") (pintype "passive"))
      (node (ref "C21") (pin "1") (pinfunction "1_1") (pintype "passive"))
      (node (ref "C22") (pin "1") (pinfunction "1_1") (pintype "passive"))
      (node (ref "C23") (pin "1") (pinfunction "1_1") (pintype "passive"))
      (node (ref "C27") (pin "2") (pinfunction "2_2") (pintype "passive"))
      (node (ref "C28") (pin "2") (pinfunction "2_2") (pintype "passive"))
      (node (ref "C29") (pin "2") (pinfunction "2_2") (pintype "passive"))
      (node (ref "C3") (pin "1") (pinfunction "1_1") (pintype "passive"))
      (node (ref "C4") (pin "1") (pinfunction "1_1") (pintype "passive"))
      (node (ref "C41") (pin "1") (pinfunction "1_1") (pintype "passive"))
      (node (ref "C42") (pin "1") (pinfunction "1_1") (pintype "passive"))
      (node (ref "C43") (pin "1") (pinfunction "1_1") (pintype "passive"))
      (node (ref "C48") (pin "2") (pinfunction "2_2") (pintype "passive"))
      (node (ref "C49") (pin "2") (pinfunction "2_2") (pintype "passive"))
      (node (ref "C5") (pin "1") (pinfunction "1_1") (pintype "passive"))
      (node (ref "C50") (pin "2") (pinfunction "2_2") (pintype "passive"))
      (node (ref "C9") (pin "2") (pinfunction "2_2") (pintype "passive"))
      (node (ref "J22") (pin "1") (pinfunction "1_1") (pintype "passive"))
      (node (ref "J22") (pin "10") (pinfunction "10_10") (pintype "passive"))
      (node (ref "J22") (pin "2") (pinfunction "2_2") (pintype "passive"))
      (node (ref "J22") (pin "3") (pinfunction "3_3") (pintype "passive"))
      (node (ref "J22") (pin "4") (pinfunction "4_4") (pintype "passive"))
      (node (ref "J22") (pin "5") (pinfunction "5_5") (pintype "passive"))
      (node (ref "J22") (pin "6") (pinfunction "6_6") (pintype "passive"))
      (node (ref "J22") (pin "7") (pinfunction "7_7") (pintype "passive"))
      (node (ref "J22") (pin "8") (pinfunction "8_8") (pintype "passive"))
      (node (ref "J22") (pin "9") (pinfunction "9_9") (pintype "passive"))
      (node (ref "J3") (pin "1") (pinfunction "1_1") (pintype "passive"))
      (node (ref "Q13") (pin "SOURCE") (pinfunction "SOURCE_SOURCE") (pintype "passive"))
      (node (ref "Q14") (pin "SOURCE") (pinfunction "SOURCE_SOURCE") (pintype "passive"))
      (node (ref "Q15") (pin "SOURCE") (pinfunction "SOURCE_SOURCE") (pintype "passive"))
      (node (ref "Q16") (pin "SOURCE") (pinfunction "SOURCE_SOURCE") (pintype "passive"))
      (node (ref "Q21") (pin "SOURCE") (pinfunction "SOURCE_SOURCE") (pintype "passive"))
      (node (ref "Q22") (pin "SOURCE") (pinfunction "SOURCE_SOURCE") (pintype "passive"))
      (node (ref "Q23") (pin "SOURCE") (pinfunction "SOURCE_SOURCE") (pintype "passive"))
      (node (ref "Q24") (pin "SOURCE") (pinfunction "SOURCE_SOURCE") (pintype "passive"))
      (node (ref "Q5") (pin "SOURCE") (pinfunction "SOURCE_SOURCE") (pintype "passive"))
      (node (ref "Q6") (pin "SOURCE") (pinfunction "SOURCE_SOURCE") (pintype "passive"))
      (node (ref "Q7") (pin "SOURCE") (pinfunction "SOURCE_SOURCE") (pintype "passive"))
      (node (ref "Q8") (pin "SOURCE") (pinfunction "SOURCE_SOURCE") (pintype "passive"))
    )
    (net (code "20") (name "VIN+") (class "Default")
      (node (ref "C10") (pin "1") (pinfunction "1_1") (pintype "passive"))
      (node (ref "C11") (pin "1") (pinfunction "1_1") (pintype "passive"))
      (node (ref "C21") (pin "2") (pinfunction "2_2") (pintype "passive"))
      (node (ref "C22") (pin "2") (pinfunction "2_2") (pintype "passive"))
      (node (ref "C23") (pin "2") (pinfunction "2_2") (pintype "passive"))
      (node (ref "C27") (pin "1") (pinfunction "1_1") (pintype "passive"))
      (node (ref "C28") (pin "1") (pinfunction "1_1") (pintype "passive"))
      (node (ref "C29") (pin "1") (pinfunction "1_1") (pintype "passive"))
      (node (ref "C3") (pin "2") (pinfunction "2_2") (pintype "passive"))
      (node (ref "C4") (pin "2") (pinfunction "2_2") (pintype "passive"))
      (node (ref "C41") (pin "2") (pinfunction "2_2") (pintype "passive"))
      (node (ref "C42") (pin "2") (pinfunction "2_2") (pintype "passive"))
      (node (ref "C43") (pin "2") (pinfunction "2_2") (pintype "passive"))
      (node (ref "C48") (pin "1") (pinfunction "1_1") (pintype "passive"))
      (node (ref "C49") (pin "1") (pinfunction "1_1") (pintype "passive"))
      (node (ref "C5") (pin "2") (pinfunction "2_2") (pintype "passive"))
      (node (ref "C50") (pin "1") (pinfunction "1_1") (pintype "passive"))
      (node (ref "C9") (pin "1") (pinfunction "1_1") (pintype "passive"))
      (node (ref "J2") (pin "1") (pinfunction "1_1") (pintype "passive"))
      (node (ref "J21") (pin "1") (pinfunction "1_1") (pintype "passive"))
      (node (ref "J21") (pin "10") (pinfunction "10_10") (pintype "passive"))
      (node (ref "J21") (pin "2") (pinfunction "2_2") (pintype "passive"))
      (node (ref "J21") (pin "3") (pinfunction "3_3") (pintype "passive"))
      (node (ref "J21") (pin "4") (pinfunction "4_4") (pintype "passive"))
      (node (ref "J21") (pin "5") (pinfunction "5_5") (pintype "passive"))
      (node (ref "J21") (pin "6") (pinfunction "6_6") (pintype "passive"))
      (node (ref "J21") (pin "7") (pinfunction "7_7") (pintype "passive"))
      (node (ref "J21") (pin "8") (pinfunction "8_8") (pintype "passive"))
      (node (ref "J21") (pin "9") (pinfunction "9_9") (pintype "passive"))
      (node (ref "Q1") (pin "DRAIN") (pinfunction "DRAIN_DRAIN") (pintype "passive"))
      (node (ref "Q10") (pin "DRAIN") (pinfunction "DRAIN_DRAIN") (pintype "passive"))
      (node (ref "Q11") (pin "DRAIN") (pinfunction "DRAIN_DRAIN") (pintype "passive"))
      (node (ref "Q12") (pin "DRAIN") (pinfunction "DRAIN_DRAIN") (pintype "passive"))
      (node (ref "Q17") (pin "DRAIN") (pinfunction "DRAIN_DRAIN") (pintype "passive"))
      (node (ref "Q18") (pin "DRAIN") (pinfunction "DRAIN_DRAIN") (pintype "passive"))
      (node (ref "Q19") (pin "DRAIN") (pinfunction "DRAIN_DRAIN") (pintype "passive"))
      (node (ref "Q2") (pin "DRAIN") (pinfunction "DRAIN_DRAIN") (pintype "passive"))
      (node (ref "Q20") (pin "DRAIN") (pinfunction "DRAIN_DRAIN") (pintype "passive"))
      (node (ref "Q3") (pin "DRAIN") (pinfunction "DRAIN_DRAIN") (pintype "passive"))
      (node (ref "Q4") (pin "DRAIN") (pinfunction "DRAIN_DRAIN") (pintype "passive"))
      (node (ref "Q9") (pin "DRAIN") (pinfunction "DRAIN_DRAIN") (pintype "passive"))
    )
  )
)
